# CONNECTOR_B.net
KiCad netlist of a schematic drawn in Altium Designer
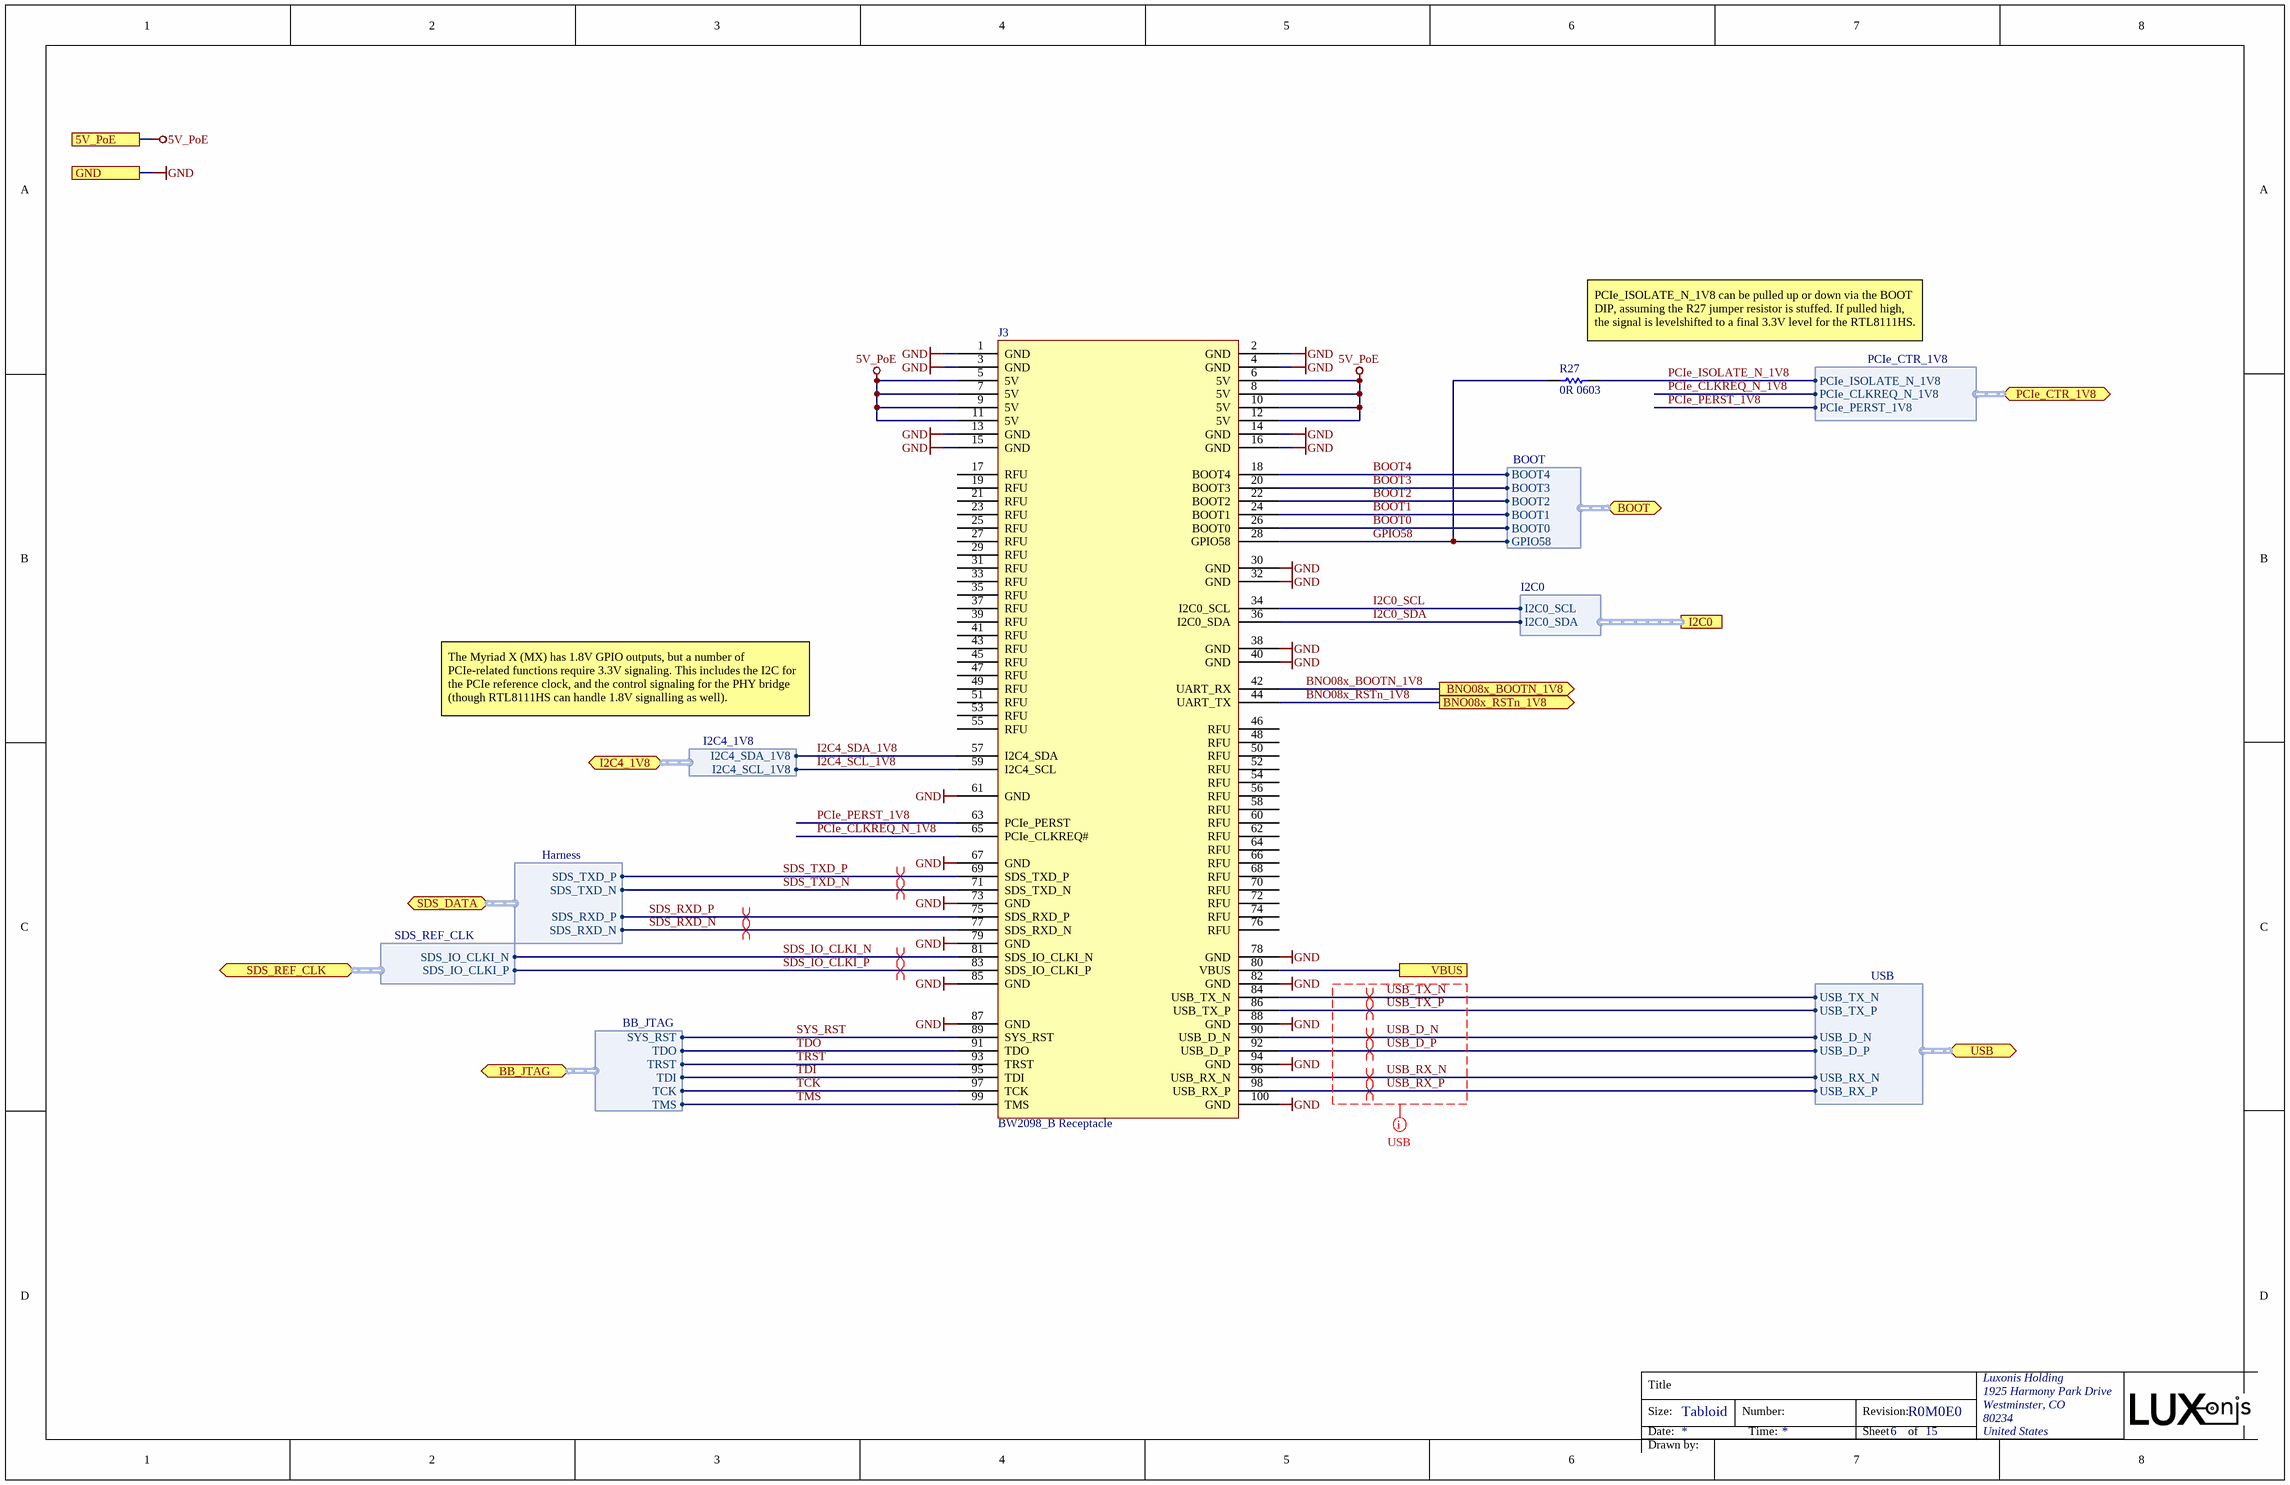
[diagram p0: CONNECTOR_B.SchDoc]

(export (version "E")
  (design (tool "Eeschema 10.0.6"))
  (components
    (comp (ref "J3")
      (value "BW2098_B Receptacle")
      (footprint "LuxonisMaster:DF40HC-3.0-100DS-0.4V_minpad")
      (description "CONN RCPT 100POS 0.4MM SMD GOLD BW2098_B Receptacle")
      (libsource (lib "BW2098POE") (part "DF40HC(3.0)-100DS-0.4V_BW2098_B"))
    )
    (comp (ref "R27")
      (value "0R 0603")
      (footprint "RESC0603(1608)_N")
      (fields (field (name "TOLERANCE") "5%"))
      (libsource (lib "LuxonisMaster") (part "CRCW06030000Z0EA"))
    )
  )
  (nets
    (net (code "9") (name "/BNO08x_BOOTN_1V8") (class "Default")
      (node (ref "J3") (pin "42") (pinfunction "UART_RX_42") (pintype "passive"))
    )
    (net (code "10") (name "/BNO08x_RSTn_1V8") (class "Default")
      (node (ref "J3") (pin "44") (pinfunction "UART_TX_44") (pintype "passive"))
    )
    (net (code "11") (name "/BOOT0") (class "Default")
      (node (ref "J3") (pin "26") (pinfunction "BOOT0_26") (pintype "passive"))
    )
    (net (code "12") (name "/BOOT1") (class "Default")
      (node (ref "J3") (pin "24") (pinfunction "BOOT1_24") (pintype "passive"))
    )
    (net (code "13") (name "/BOOT2") (class "Default")
      (node (ref "J3") (pin "22") (pinfunction "BOOT2_22") (pintype "passive"))
    )
    (net (code "14") (name "/BOOT3") (class "Default")
      (node (ref "J3") (pin "20") (pinfunction "BOOT3_20") (pintype "passive"))
    )
    (net (code "15") (name "/BOOT4") (class "Default")
      (node (ref "J3") (pin "18") (pinfunction "BOOT4_18") (pintype "passive"))
    )
    (net (code "16") (name "/GPIO58") (class "Default")
      (node (ref "J3") (pin "28") (pinfunction "GPIO58_28") (pintype "passive"))
      (node (ref "R27") (pin "1") (pinfunction "1_1") (pintype "passive"))
    )
    (net (code "17") (name "/I2C0_SCL") (class "Default")
      (node (ref "J3") (pin "34") (pinfunction "I2C0_SCL_34") (pintype "passive"))
    )
    (net (code "18") (name "/I2C0_SDA") (class "Default")
      (node (ref "J3") (pin "36") (pinfunction "I2C0_SDA_36") (pintype "passive"))
    )
    (net (code "19") (name "/I2C4_SCL_1V8") (class "Default")
      (node (ref "J3") (pin "59") (pinfunction "I2C4_SCL_59") (pintype "passive"))
    )
    (net (code "20") (name "/I2C4_SDA_1V8") (class "Default")
      (node (ref "J3") (pin "57") (pinfunction "I2C4_SDA_57") (pintype "passive"))
    )
    (net (code "21") (name "/PCIe_CLKREQ_N_1V8") (class "Default")
      (node (ref "J3") (pin "65") (pinfunction "PCIe_CLKREQ#_65") (pintype "passive"))
    )
    (net (code "22") (name "/PCIe_ISOLATE_N_1V8") (class "Default")
      (node (ref "R27") (pin "2") (pinfunction "2_2") (pintype "passive"))
    )
    (net (code "23") (name "/PCIe_PERST_1V8") (class "Default")
      (node (ref "J3") (pin "63") (pinfunction "PCIe_PERST_63") (pintype "passive"))
    )
    (net (code "24") (name "/SDS_IO_CLKI_N") (class "Default")
      (node (ref "J3") (pin "81") (pinfunction "SDS_IO_CLKI_N_81") (pintype "passive"))
    )
    (net (code "25") (name "/SDS_IO_CLKI_P") (class "Default")
      (node (ref "J3") (pin "83") (pinfunction "SDS_IO_CLKI_P_83") (pintype "passive"))
    )
    (net (code "26") (name "/SDS_RXD_N") (class "Default")
      (node (ref "J3") (pin "77") (pinfunction "SDS_RXD_N_77") (pintype "passive"))
    )
    (net (code "27") (name "/SDS_RXD_P") (class "Default")
      (node (ref "J3") (pin "75") (pinfunction "SDS_RXD_P_75") (pintype "passive"))
    )
    (net (code "28") (name "/SDS_TXD_N") (class "Default")
      (node (ref "J3") (pin "71") (pinfunction "SDS_TXD_N_71") (pintype "passive"))
    )
    (net (code "29") (name "/SDS_TXD_P") (class "Default")
      (node (ref "J3") (pin "69") (pinfunction "SDS_TXD_P_69") (pintype "passive"))
    )
    (net (code "30") (name "/SYS_RST") (class "Default")
      (node (ref "J3") (pin "89") (pinfunction "SYS_RST_89") (pintype "passive"))
    )
    (net (code "31") (name "/TCK") (class "Default")
      (node (ref "J3") (pin "97") (pinfunction "TCK_97") (pintype "passive"))
    )
    (net (code "32") (name "/TDI") (class "Default")
      (node (ref "J3") (pin "95") (pinfunction "TDI_95") (pintype "passive"))
    )
    (net (code "33") (name "/TDO") (class "Default")
      (node (ref "J3") (pin "91") (pinfunction "TDO_91") (pintype "passive"))
    )
    (net (code "34") (name "/TMS") (class "Default")
      (node (ref "J3") (pin "99") (pinfunction "TMS_99") (pintype "passive"))
    )
    (net (code "35") (name "/TRST") (class "Default")
      (node (ref "J3") (pin "93") (pinfunction "TRST_93") (pintype "passive"))
    )
    (net (code "36") (name "/USB_D_N") (class "Default")
      (node (ref "J3") (pin "90") (pinfunction "USB_D_N_90") (pintype "passive"))
    )
    (net (code "37") (name "/USB_D_P") (class "Default")
      (node (ref "J3") (pin "92") (pinfunction "USB_D_P_92") (pintype "passive"))
    )
    (net (code "38") (name "/USB_RX_N") (class "Default")
      (node (ref "J3") (pin "96") (pinfunction "USB_RX_N_96") (pintype "passive"))
    )
    (net (code "39") (name "/USB_RX_P") (class "Default")
      (node (ref "J3") (pin "98") (pinfunction "USB_RX_P_98") (pintype "passive"))
    )
    (net (code "40") (name "/USB_TX_N") (class "Default")
      (node (ref "J3") (pin "84") (pinfunction "USB_TX_N_84") (pintype "passive"))
    )
    (net (code "41") (name "/USB_TX_P") (class "Default")
      (node (ref "J3") (pin "86") (pinfunction "USB_TX_P_86") (pintype "passive"))
    )
    (net (code "42") (name "/VBUS") (class "Default")
      (node (ref "J3") (pin "80") (pinfunction "VBUS_80") (pintype "passive"))
    )
    (net (code "51") (name "5V_PoE") (class "Default")
      (node (ref "J3") (pin "10") (pinfunction "5V_10") (pintype "passive"))
      (node (ref "J3") (pin "11") (pinfunction "5V_11") (pintype "passive"))
      (node (ref "J3") (pin "12") (pinfunction "5V_12") (pintype "passive"))
      (node (ref "J3") (pin "5") (pinfunction "5V_5") (pintype "passive"))
      (node (ref "J3") (pin "6") (pinfunction "5V_6") (pintype "passive"))
      (node (ref "J3") (pin "7") (pinfunction "5V_7") (pintype "passive"))
      (node (ref "J3") (pin "8") (pinfunction "5V_8") (pintype "passive"))
      (node (ref "J3") (pin "9") (pinfunction "5V_9") (pintype "passive"))
    )
    (net (code "52") (name "GND") (class "Default")
      (node (ref "J3") (pin "1") (pinfunction "GND_1") (pintype "passive"))
      (node (ref "J3") (pin "100") (pinfunction "GND_100") (pintype "passive"))
      (node (ref "J3") (pin "13") (pinfunction "GND_13") (pintype "passive"))
      (node (ref "J3") (pin "14") (pinfunction "GND_14") (pintype "passive"))
      (node (ref "J3") (pin "15") (pinfunction "GND_15") (pintype "passive"))
      (node (ref "J3") (pin "16") (pinfunction "GND_16") (pintype "passive"))
      (node (ref "J3") (pin "2") (pinfunction "GND_2") (pintype "passive"))
      (node (ref "J3") (pin "3") (pinfunction "GND_3") (pintype "passive"))
      (node (ref "J3") (pin "30") (pinfunction "GND_30") (pintype "passive"))
      (node (ref "J3") (pin "32") (pinfunction "GND_32") (pintype "passive"))
      (node (ref "J3") (pin "38") (pinfunction "GND_38") (pintype "passive"))
      (node (ref "J3") (pin "4") (pinfunction "GND_4") (pintype "passive"))
      (node (ref "J3") (pin "40") (pinfunction "GND_40") (pintype "passive"))
      (node (ref "J3") (pin "61") (pinfunction "GND_61") (pintype "passive"))
      (node (ref "J3") (pin "67") (pinfunction "GND_67") (pintype "passive"))
      (node (ref "J3") (pin "73") (pinfunction "GND_73") (pintype "passive"))
      (node (ref "J3") (pin "78") (pinfunction "GND_78") (pintype "passive"))
      (node (ref "J3") (pin "79") (pinfunction "GND_79") (pintype "passive"))
      (node (ref "J3") (pin "82") (pinfunction "GND_82") (pintype "passive"))
      (node (ref "J3") (pin "85") (pinfunction "GND_85") (pintype "passive"))
      (node (ref "J3") (pin "87") (pinfunction "GND_87") (pintype "passive"))
      (node (ref "J3") (pin "88") (pinfunction "GND_88") (pintype "passive"))
      (node (ref "J3") (pin "94") (pinfunction "GND_94") (pintype "passive"))
    )
    (net (code "53") (name "unconnected-(J3-RFU-Pad17)") (class "Default")
      (node (ref "J3") (pin "17") (pinfunction "RFU_17") (pintype "passive"))
    )
    (net (code "54") (name "unconnected-(J3-RFU-Pad19)") (class "Default")
      (node (ref "J3") (pin "19") (pinfunction "RFU_19") (pintype "passive"))
    )
    (net (code "55") (name "unconnected-(J3-RFU-Pad21)") (class "Default")
      (node (ref "J3") (pin "21") (pinfunction "RFU_21") (pintype "passive"))
    )
    (net (code "56") (name "unconnected-(J3-RFU-Pad23)") (class "Default")
      (node (ref "J3") (pin "23") (pinfunction "RFU_23") (pintype "passive"))
    )
    (net (code "57") (name "unconnected-(J3-RFU-Pad25)") (class "Default")
      (node (ref "J3") (pin "25") (pinfunction "RFU_25") (pintype "passive"))
    )
    (net (code "58") (name "unconnected-(J3-RFU-Pad27)") (class "Default")
      (node (ref "J3") (pin "27") (pinfunction "RFU_27") (pintype "passive"))
    )
    (net (code "59") (name "unconnected-(J3-RFU-Pad29)") (class "Default")
      (node (ref "J3") (pin "29") (pinfunction "RFU_29") (pintype "passive"))
    )
    (net (code "60") (name "unconnected-(J3-RFU-Pad31)") (class "Default")
      (node (ref "J3") (pin "31") (pinfunction "RFU_31") (pintype "passive"))
    )
    (net (code "61") (name "unconnected-(J3-RFU-Pad33)") (class "Default")
      (node (ref "J3") (pin "33") (pinfunction "RFU_33") (pintype "passive"))
    )
    (net (code "62") (name "unconnected-(J3-RFU-Pad35)") (class "Default")
      (node (ref "J3") (pin "35") (pinfunction "RFU_35") (pintype "passive"))
    )
    (net (code "63") (name "unconnected-(J3-RFU-Pad37)") (class "Default")
      (node (ref "J3") (pin "37") (pinfunction "RFU_37") (pintype "passive"))
    )
    (net (code "64") (name "unconnected-(J3-RFU-Pad39)") (class "Default")
      (node (ref "J3") (pin "39") (pinfunction "RFU_39") (pintype "passive"))
    )
    (net (code "65") (name "unconnected-(J3-RFU-Pad41)") (class "Default")
      (node (ref "J3") (pin "41") (pinfunction "RFU_41") (pintype "passive"))
    )
    (net (code "66") (name "unconnected-(J3-RFU-Pad43)") (class "Default")
      (node (ref "J3") (pin "43") (pinfunction "RFU_43") (pintype "passive"))
    )
    (net (code "67") (name "unconnected-(J3-RFU-Pad45)") (class "Default")
      (node (ref "J3") (pin "45") (pinfunction "RFU_45") (pintype "passive"))
    )
    (net (code "68") (name "unconnected-(J3-RFU-Pad46)") (class "Default")
      (node (ref "J3") (pin "46") (pinfunction "RFU_46") (pintype "passive"))
    )
    (net (code "69") (name "unconnected-(J3-RFU-Pad47)") (class "Default")
      (node (ref "J3") (pin "47") (pinfunction "RFU_47") (pintype "passive"))
    )
    (net (code "70") (name "unconnected-(J3-RFU-Pad48)") (class "Default")
      (node (ref "J3") (pin "48") (pinfunction "RFU_48") (pintype "passive"))
    )
    (net (code "71") (name "unconnected-(J3-RFU-Pad49)") (class "Default")
      (node (ref "J3") (pin "49") (pinfunction "RFU_49") (pintype "passive"))
    )
    (net (code "72") (name "unconnected-(J3-RFU-Pad50)") (class "Default")
      (node (ref "J3") (pin "50") (pinfunction "RFU_50") (pintype "passive"))
    )
    (net (code "73") (name "unconnected-(J3-RFU-Pad51)") (class "Default")
      (node (ref "J3") (pin "51") (pinfunction "RFU_51") (pintype "passive"))
    )
    (net (code "74") (name "unconnected-(J3-RFU-Pad52)") (class "Default")
      (node (ref "J3") (pin "52") (pinfunction "RFU_52") (pintype "passive"))
    )
    (net (code "75") (name "unconnected-(J3-RFU-Pad53)") (class "Default")
      (node (ref "J3") (pin "53") (pinfunction "RFU_53") (pintype "passive"))
    )
    (net (code "76") (name "unconnected-(J3-RFU-Pad54)") (class "Default")
      (node (ref "J3") (pin "54") (pinfunction "RFU_54") (pintype "passive"))
    )
    (net (code "77") (name "unconnected-(J3-RFU-Pad55)") (class "Default")
      (node (ref "J3") (pin "55") (pinfunction "RFU_55") (pintype "passive"))
    )
    (net (code "78") (name "unconnected-(J3-RFU-Pad56)") (class "Default")
      (node (ref "J3") (pin "56") (pinfunction "RFU_56") (pintype "passive"))
    )
    (net (code "79") (name "unconnected-(J3-RFU-Pad58)") (class "Default")
      (node (ref "J3") (pin "58") (pinfunction "RFU_58") (pintype "passive"))
    )
    (net (code "80") (name "unconnected-(J3-RFU-Pad60)") (class "Default")
      (node (ref "J3") (pin "60") (pinfunction "RFU_60") (pintype "passive"))
    )
    (net (code "81") (name "unconnected-(J3-RFU-Pad62)") (class "Default")
      (node (ref "J3") (pin "62") (pinfunction "RFU_62") (pintype "passive"))
    )
    (net (code "82") (name "unconnected-(J3-RFU-Pad64)") (class "Default")
      (node (ref "J3") (pin "64") (pinfunction "RFU_64") (pintype "passive"))
    )
    (net (code "83") (name "unconnected-(J3-RFU-Pad66)") (class "Default")
      (node (ref "J3") (pin "66") (pinfunction "RFU_66") (pintype "passive"))
    )
    (net (code "84") (name "unconnected-(J3-RFU-Pad68)") (class "Default")
      (node (ref "J3") (pin "68") (pinfunction "RFU_68") (pintype "passive"))
    )
    (net (code "85") (name "unconnected-(J3-RFU-Pad70)") (class "Default")
      (node (ref "J3") (pin "70") (pinfunction "RFU_70") (pintype "passive"))
    )
    (net (code "86") (name "unconnected-(J3-RFU-Pad72)") (class "Default")
      (node (ref "J3") (pin "72") (pinfunction "RFU_72") (pintype "passive"))
    )
    (net (code "87") (name "unconnected-(J3-RFU-Pad74)") (class "Default")
      (node (ref "J3") (pin "74") (pinfunction "RFU_74") (pintype "passive"))
    )
    (net (code "88") (name "unconnected-(J3-RFU-Pad76)") (class "Default")
      (node (ref "J3") (pin "76") (pinfunction "RFU_76") (pintype "passive"))
    )
  )
)
